# LiPoChargerBooster5V1A_v10.net
KiCad netlist of a schematic drawn in EAGLE
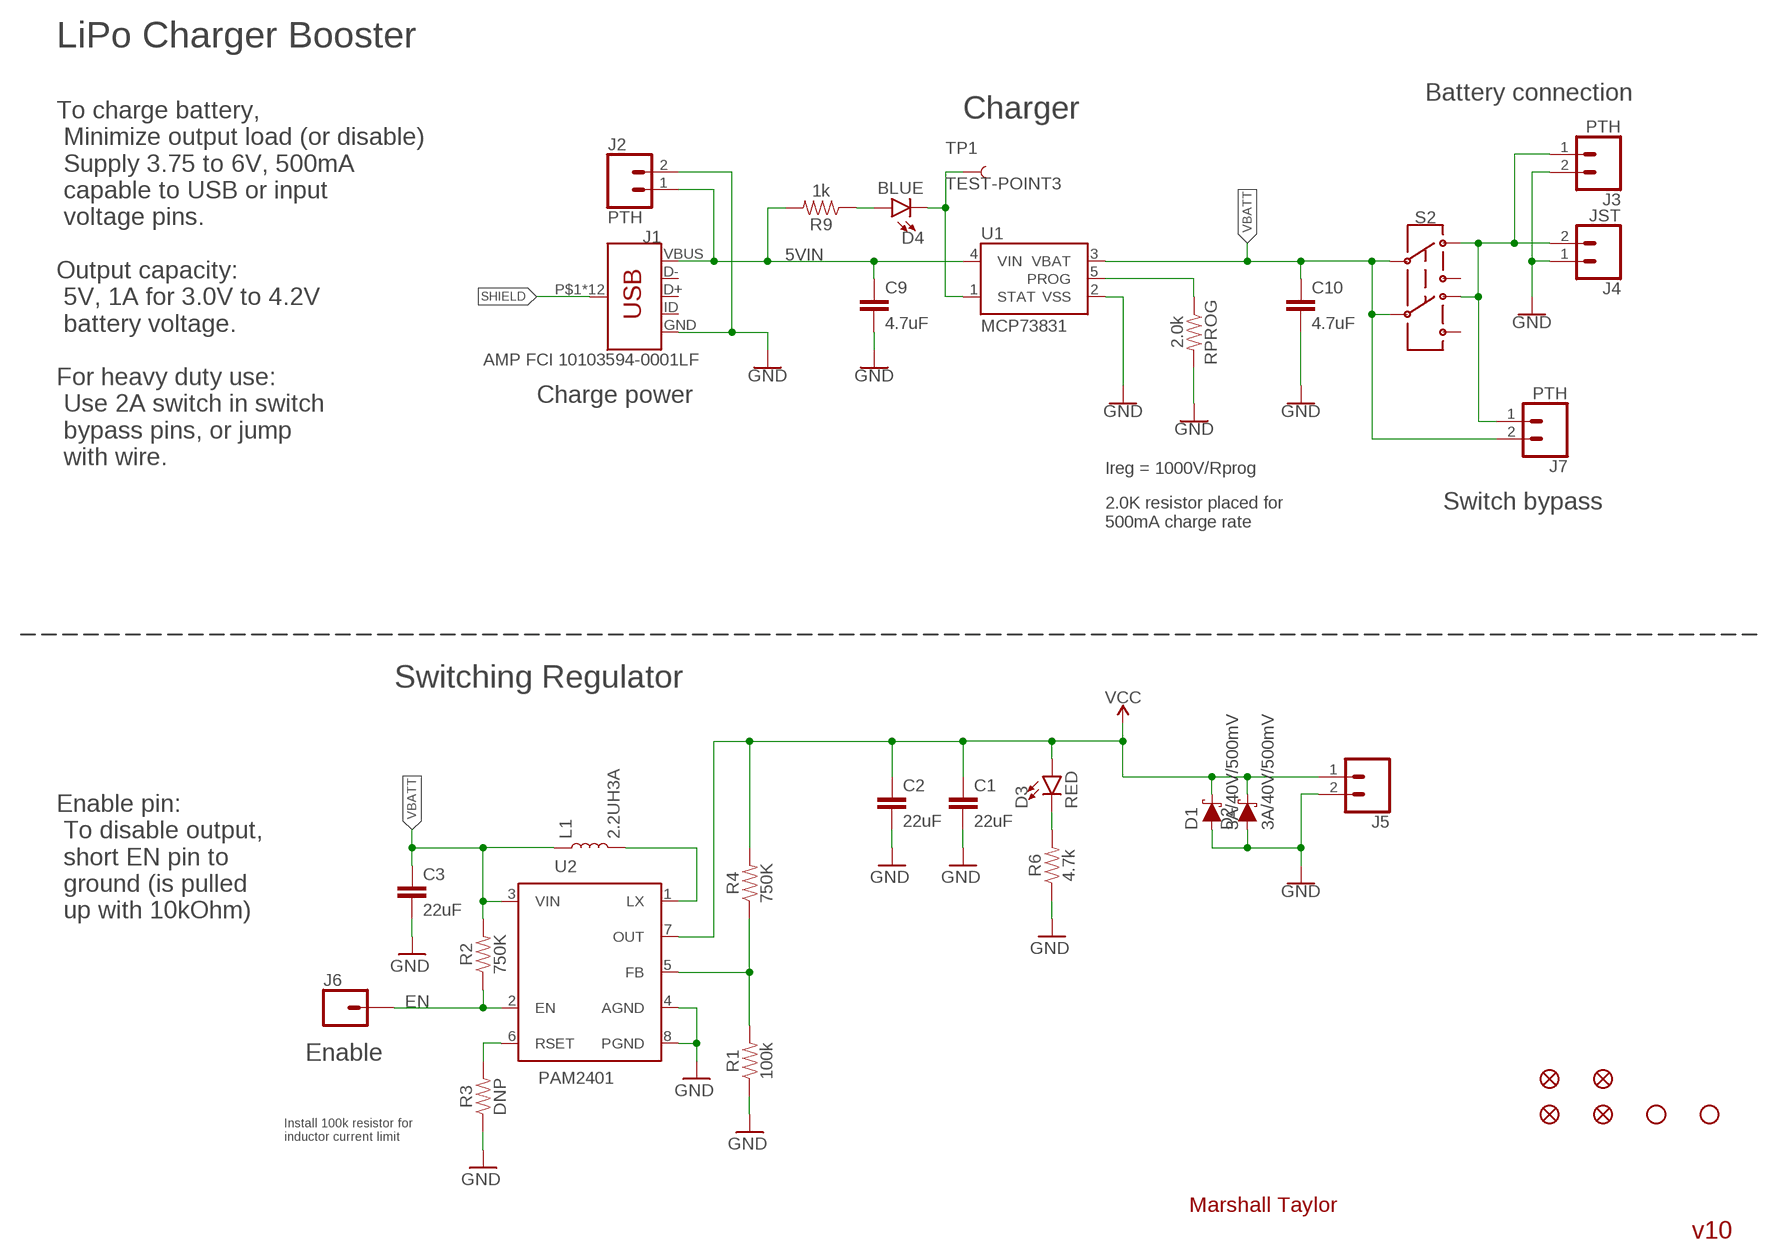
[diagram p0: schematic, sheet 1]

(export (version "E")
  (design (tool "Eeschema 10.0.6"))
  (components
    (comp (ref "C1")
      (value "22uF")
      (footprint "eagle-import:0805")
      (libsource (lib "eagle-import") (part "22UF-0805-6.3V-20%"))
    )
    (comp (ref "C2")
      (value "22uF")
      (footprint "eagle-import:0805")
      (libsource (lib "eagle-import") (part "22UF-0805-6.3V-20%"))
    )
    (comp (ref "C3")
      (value "22uF")
      (footprint "eagle-import:0805")
      (libsource (lib "eagle-import") (part "22UF-0805-6.3V-20%"))
    )
    (comp (ref "C9")
      (value "4.7uF")
      (footprint "eagle-import:0603")
      (libsource (lib "eagle-import") (part "4.7UF0603"))
    )
    (comp (ref "C10")
      (value "4.7uF")
      (footprint "eagle-import:0603")
      (libsource (lib "eagle-import") (part "4.7UF0603"))
    )
    (comp (ref "D1")
      (value "3A/40V/500mV")
      (footprint "eagle-import:SMA-DIODE")
      (libsource (lib "eagle-import") (part "DIODE-SCHOTTKY-B340A"))
    )
    (comp (ref "D2")
      (value "3A/40V/500mV")
      (footprint "eagle-import:SMA-DIODE")
      (libsource (lib "eagle-import") (part "DIODE-SCHOTTKY-B340A"))
    )
    (comp (ref "D3")
      (value "RED")
      (footprint "eagle-import:LED-0603")
      (libsource (lib "eagle-import") (part "LED-RED0603"))
    )
    (comp (ref "D4")
      (value "BLUE")
      (footprint "eagle-import:LED-0603")
      (libsource (lib "eagle-import") (part "LED-BLUE0603"))
    )
    (comp (ref "J1")
      (value "AMP FCI 10103594-0001LF")
      (footprint "eagle-import:USB-MICROB-PTH")
      (libsource (lib "eagle-import") (part "USB_MICRO-B_HALF_PTH"))
    )
    (comp (ref "J2")
      (value "PTH")
      (footprint "eagle-import:1X02")
      (libsource (lib "eagle-import") (part "CONN_02"))
    )
    (comp (ref "J3")
      (value "PTH")
      (footprint "eagle-import:1X02")
      (libsource (lib "eagle-import") (part "CONN_02"))
    )
    (comp (ref "J4")
      (value "JST")
      (footprint "eagle-import:JST-2-SMD")
      (libsource (lib "eagle-import") (part "CONN_02-JST-2MM-SMT"))
    )
    (comp (ref "J5")
      (value "CONN_02")
      (footprint "eagle-import:1X02")
      (libsource (lib "eagle-import") (part "CONN_02"))
    )
    (comp (ref "J6")
      (value "CONN_01")
      (footprint "eagle-import:1X01")
      (libsource (lib "eagle-import") (part "CONN_01"))
    )
    (comp (ref "J7")
      (value "PTH")
      (footprint "eagle-import:1X02")
      (libsource (lib "eagle-import") (part "CONN_02"))
    )
    (comp (ref "JP1")
      (value "FIDUCIAL1X2")
      (footprint "eagle-import:FIDUCIAL-1X2")
      (libsource (lib "eagle-import") (part "FIDUCIAL1X2"))
    )
    (comp (ref "JP2")
      (value "FIDUCIAL1X2")
      (footprint "eagle-import:FIDUCIAL-1X2")
      (libsource (lib "eagle-import") (part "FIDUCIAL1X2"))
    )
    (comp (ref "JP4")
      (value "FIDUCIAL1X2")
      (footprint "eagle-import:FIDUCIAL-1X2")
      (libsource (lib "eagle-import") (part "FIDUCIAL1X2"))
    )
    (comp (ref "JP6")
      (value "STAND-OFF")
      (footprint "eagle-import:STAND-OFF")
      (libsource (lib "eagle-import") (part "STAND-OFF"))
    )
    (comp (ref "JP7")
      (value "STAND-OFF")
      (footprint "eagle-import:STAND-OFF")
      (libsource (lib "eagle-import") (part "STAND-OFF"))
    )
    (comp (ref "JP16")
      (value "FIDUCIAL1X2")
      (footprint "eagle-import:FIDUCIAL-1X2")
      (libsource (lib "eagle-import") (part "FIDUCIAL1X2"))
    )
    (comp (ref "L1")
      (value "2.2UH3A")
      (footprint "eagle-import:INDUCTOR_4X4MM")
      (libsource (lib "eagle-import") (part "INDUCTOR-IFSC1515AHER2R2M01"))
    )
    (comp (ref "R1")
      (value "100k")
      (footprint "eagle-import:0603")
      (libsource (lib "eagle-import") (part "100KOHM-0603-1/10W-1%"))
    )
    (comp (ref "R2")
      (value "750K")
      (footprint "eagle-import:0603")
      (libsource (lib "eagle-import") (part "750KOHM-0603-1/10W-1%"))
    )
    (comp (ref "R3")
      (value "DNP")
      (footprint "eagle-import:0603")
      (libsource (lib "eagle-import") (part "100KOHM-0603-1/10W-1%"))
    )
    (comp (ref "R4")
      (value "750K")
      (footprint "eagle-import:0603")
      (libsource (lib "eagle-import") (part "750KOHM-0603-1/10W-1%"))
    )
    (comp (ref "R6")
      (value "4.7k")
      (footprint "eagle-import:0603")
      (libsource (lib "eagle-import") (part "4.7KOHM-0603-1/10W-1%"))
    )
    (comp (ref "R9")
      (value "1k")
      (footprint "eagle-import:0603")
      (libsource (lib "eagle-import") (part "1KOHM-0603-1/10W-1%"))
    )
    (comp (ref "RPROG")
      (value "2.0k")
      (footprint "eagle-import:0603")
      (libsource (lib "eagle-import") (part "2.0KOHM-0603-1/10W-5%"))
    )
    (comp (ref "S2")
      (value "SWITCH-DPDT-SMD-AYZ0202")
      (footprint "eagle-import:SWITCH_DPDT_SMD_AYZ0202")
      (libsource (lib "eagle-import") (part "SWITCH-DPDT-SMD-AYZ0202"))
    )
    (comp (ref "TP1")
      (value "TEST-POINT3")
      (footprint "eagle-import:PAD.03X.03")
      (libsource (lib "eagle-import") (part "TEST-POINT3"))
    )
    (comp (ref "U1")
      (value "MCP73831")
      (footprint "eagle-import:SOT23-5")
      (libsource (lib "eagle-import") (part "MCP73831"))
    )
    (comp (ref "U2")
      (value "PAM2401")
      (footprint "eagle-import:MSOP8")
      (libsource (lib "eagle-import") (part "PAM2401"))
    )
  )
  (nets
    (net (code "1") (name "/5VIN") (class "Default")
      (node (ref "C9") (pin "1") (pinfunction "1_1") (pintype "passive"))
      (node (ref "J1") (pin "VBUS") (pinfunction "VBUS_VBUS") (pintype "power_in"))
      (node (ref "J2") (pin "1") (pinfunction "1_1") (pintype "passive"))
      (node (ref "R9") (pin "2") (pinfunction "2_2") (pintype "passive"))
      (node (ref "U1") (pin "4") (pinfunction "VIN_4") (pintype "power_in"))
    )
    (net (code "2") (name "/EN") (class "Default")
      (node (ref "J6") (pin "1") (pinfunction "1_1") (pintype "passive"))
      (node (ref "R2") (pin "1") (pinfunction "1_1") (pintype "passive"))
      (node (ref "U2") (pin "2") (pinfunction "EN_2") (pintype "bidirectional"))
    )
    (net (code "3") (name "GND") (class "Default")
      (node (ref "C1") (pin "2") (pinfunction "2_2") (pintype "passive"))
      (node (ref "C10") (pin "2") (pinfunction "2_2") (pintype "passive"))
      (node (ref "C2") (pin "2") (pinfunction "2_2") (pintype "passive"))
      (node (ref "C3") (pin "2") (pinfunction "2_2") (pintype "passive"))
      (node (ref "C9") (pin "2") (pinfunction "2_2") (pintype "passive"))
      (node (ref "D1") (pin "A") (pinfunction "A_A") (pintype "passive"))
      (node (ref "D2") (pin "A") (pinfunction "A_A") (pintype "passive"))
      (node (ref "J1") (pin "GND") (pinfunction "GND_GND") (pintype "power_in"))
      (node (ref "J2") (pin "2") (pinfunction "2_2") (pintype "passive"))
      (node (ref "J3") (pin "2") (pinfunction "2_2") (pintype "passive"))
      (node (ref "J4") (pin "1") (pinfunction "2_1") (pintype "passive"))
      (node (ref "J5") (pin "2") (pinfunction "2_2") (pintype "passive"))
      (node (ref "R1") (pin "1") (pinfunction "1_1") (pintype "passive"))
      (node (ref "R3") (pin "1") (pinfunction "1_1") (pintype "passive"))
      (node (ref "R6") (pin "1") (pinfunction "1_1") (pintype "passive"))
      (node (ref "RPROG") (pin "2") (pinfunction "2_2") (pintype "passive"))
      (node (ref "U1") (pin "2") (pinfunction "VSS_2") (pintype "power_in"))
      (node (ref "U2") (pin "4") (pinfunction "AGND_4") (pintype "bidirectional"))
      (node (ref "U2") (pin "8") (pinfunction "PGND_8") (pintype "bidirectional"))
    )
    (net (code "4") (name "Net-(D3-PadC)") (class "Default")
      (node (ref "D3") (pin "C") (pinfunction "C_C") (pintype "passive"))
      (node (ref "R6") (pin "2") (pinfunction "2_2") (pintype "passive"))
    )
    (net (code "5") (name "Net-(D4-PadA)") (class "Default")
      (node (ref "D4") (pin "A") (pinfunction "A_A") (pintype "passive"))
      (node (ref "R9") (pin "1") (pinfunction "1_1") (pintype "passive"))
    )
    (net (code "6") (name "Net-(J4-1)") (class "Default")
      (node (ref "J3") (pin "1") (pinfunction "1_1") (pintype "passive"))
      (node (ref "J4") (pin "2") (pinfunction "1_2") (pintype "passive"))
      (node (ref "J7") (pin "1") (pinfunction "1_1") (pintype "passive"))
      (node (ref "S2") (pin "1") (pinfunction "1_1") (pintype "bidirectional"))
      (node (ref "S2") (pin "4") (pinfunction "4_4") (pintype "bidirectional"))
    )
    (net (code "7") (name "Net-(L1-2)") (class "Default")
      (node (ref "L1") (pin "P$2") (pinfunction "2_P$2") (pintype "passive"))
      (node (ref "U2") (pin "1") (pinfunction "LX_1") (pintype "bidirectional"))
    )
    (net (code "8") (name "Net-(TP1-1)") (class "Default")
      (node (ref "D4") (pin "C") (pinfunction "C_C") (pintype "passive"))
      (node (ref "TP1") (pin "P$1") (pinfunction "1_P$1") (pintype "bidirectional"))
      (node (ref "U1") (pin "1") (pinfunction "STAT_1") (pintype "output"))
    )
    (net (code "9") (name "Net-(U1-PROG)") (class "Default")
      (node (ref "RPROG") (pin "1") (pinfunction "1_1") (pintype "passive"))
      (node (ref "U1") (pin "5") (pinfunction "PROG_5") (pintype "input"))
    )
    (net (code "10") (name "Net-(U2-FB)") (class "Default")
      (node (ref "R1") (pin "2") (pinfunction "2_2") (pintype "passive"))
      (node (ref "R4") (pin "1") (pinfunction "1_1") (pintype "passive"))
      (node (ref "U2") (pin "5") (pinfunction "FB_5") (pintype "bidirectional"))
    )
    (net (code "11") (name "Net-(U2-RSET)") (class "Default")
      (node (ref "R3") (pin "2") (pinfunction "2_2") (pintype "passive"))
      (node (ref "U2") (pin "6") (pinfunction "RSET_6") (pintype "bidirectional"))
    )
    (net (code "12") (name "SHIELD") (class "Default")
      (node (ref "J1") (pin "P$1") (pinfunction "SHIELD_P$1") (pintype "bidirectional"))
      (node (ref "J1") (pin "P$10") (pinfunction "SHIELD_P$10") (pintype "bidirectional"))
      (node (ref "J1") (pin "P$12") (pinfunction "SHIELD_P$12") (pintype "bidirectional"))
      (node (ref "J1") (pin "P$2") (pinfunction "SHIELD_P$2") (pintype "bidirectional"))
      (node (ref "J1") (pin "P$3") (pinfunction "SHIELD_P$3") (pintype "bidirectional"))
      (node (ref "J1") (pin "P$4") (pinfunction "SHIELD_P$4") (pintype "bidirectional"))
      (node (ref "J1") (pin "P$6") (pinfunction "SHIELD_P$6") (pintype "bidirectional"))
      (node (ref "J1") (pin "P$8") (pinfunction "SHIELD_P$8") (pintype "bidirectional"))
      (node (ref "J1") (pin "SHEILD2") (pinfunction "SHIELD_SHEILD2") (pintype "bidirectional"))
      (node (ref "J1") (pin "SHIELD") (pinfunction "SHIELD_SHIELD") (pintype "bidirectional"))
      (node (ref "J1") (pin "SHIELD3") (pinfunction "SHIELD_SHIELD3") (pintype "bidirectional"))
      (node (ref "J1") (pin "SHIELD4") (pinfunction "SHIELD_SHIELD4") (pintype "bidirectional"))
    )
    (net (code "13") (name "VBATT") (class "Default")
      (node (ref "C10") (pin "1") (pinfunction "1_1") (pintype "passive"))
      (node (ref "C3") (pin "1") (pinfunction "1_1") (pintype "passive"))
      (node (ref "J7") (pin "2") (pinfunction "2_2") (pintype "passive"))
      (node (ref "L1") (pin "P$1") (pinfunction "1_P$1") (pintype "passive"))
      (node (ref "R2") (pin "2") (pinfunction "2_2") (pintype "passive"))
      (node (ref "S2") (pin "2") (pinfunction "2_2") (pintype "bidirectional"))
      (node (ref "S2") (pin "5") (pinfunction "5_5") (pintype "bidirectional"))
      (node (ref "U1") (pin "3") (pinfunction "VBAT_3") (pintype "power_in"))
      (node (ref "U2") (pin "3") (pinfunction "VIN_3") (pintype "bidirectional"))
    )
    (net (code "14") (name "VCC") (class "Default")
      (node (ref "C1") (pin "1") (pinfunction "1_1") (pintype "passive"))
      (node (ref "C2") (pin "1") (pinfunction "1_1") (pintype "passive"))
      (node (ref "D1") (pin "C") (pinfunction "C_C") (pintype "passive"))
      (node (ref "D2") (pin "C") (pinfunction "C_C") (pintype "passive"))
      (node (ref "D3") (pin "A") (pinfunction "A_A") (pintype "passive"))
      (node (ref "J5") (pin "1") (pinfunction "1_1") (pintype "passive"))
      (node (ref "R4") (pin "2") (pinfunction "2_2") (pintype "passive"))
      (node (ref "U2") (pin "7") (pinfunction "OUT_7") (pintype "bidirectional"))
    )
    (net (code "15") (name "unconnected-(J1-PadD+)") (class "Default")
      (node (ref "J1") (pin "D+") (pinfunction "D+_D+") (pintype "bidirectional"))
    )
    (net (code "16") (name "unconnected-(J1-PadD-)") (class "Default")
      (node (ref "J1") (pin "D-") (pinfunction "D-_D-") (pintype "bidirectional"))
    )
    (net (code "17") (name "unconnected-(J1-PadID)") (class "Default")
      (node (ref "J1") (pin "ID") (pinfunction "ID_ID") (pintype "bidirectional"))
    )
    (net (code "18") (name "unconnected-(S2-Pad3)") (class "Default")
      (node (ref "S2") (pin "3") (pinfunction "3_3") (pintype "bidirectional"))
    )
    (net (code "19") (name "unconnected-(S2-Pad6)") (class "Default")
      (node (ref "S2") (pin "6") (pinfunction "6_6") (pintype "bidirectional"))
    )
  )
)
